# Sheet_1_2023-09-05.net
KiCad netlist of a schematic drawn in Altium Designer
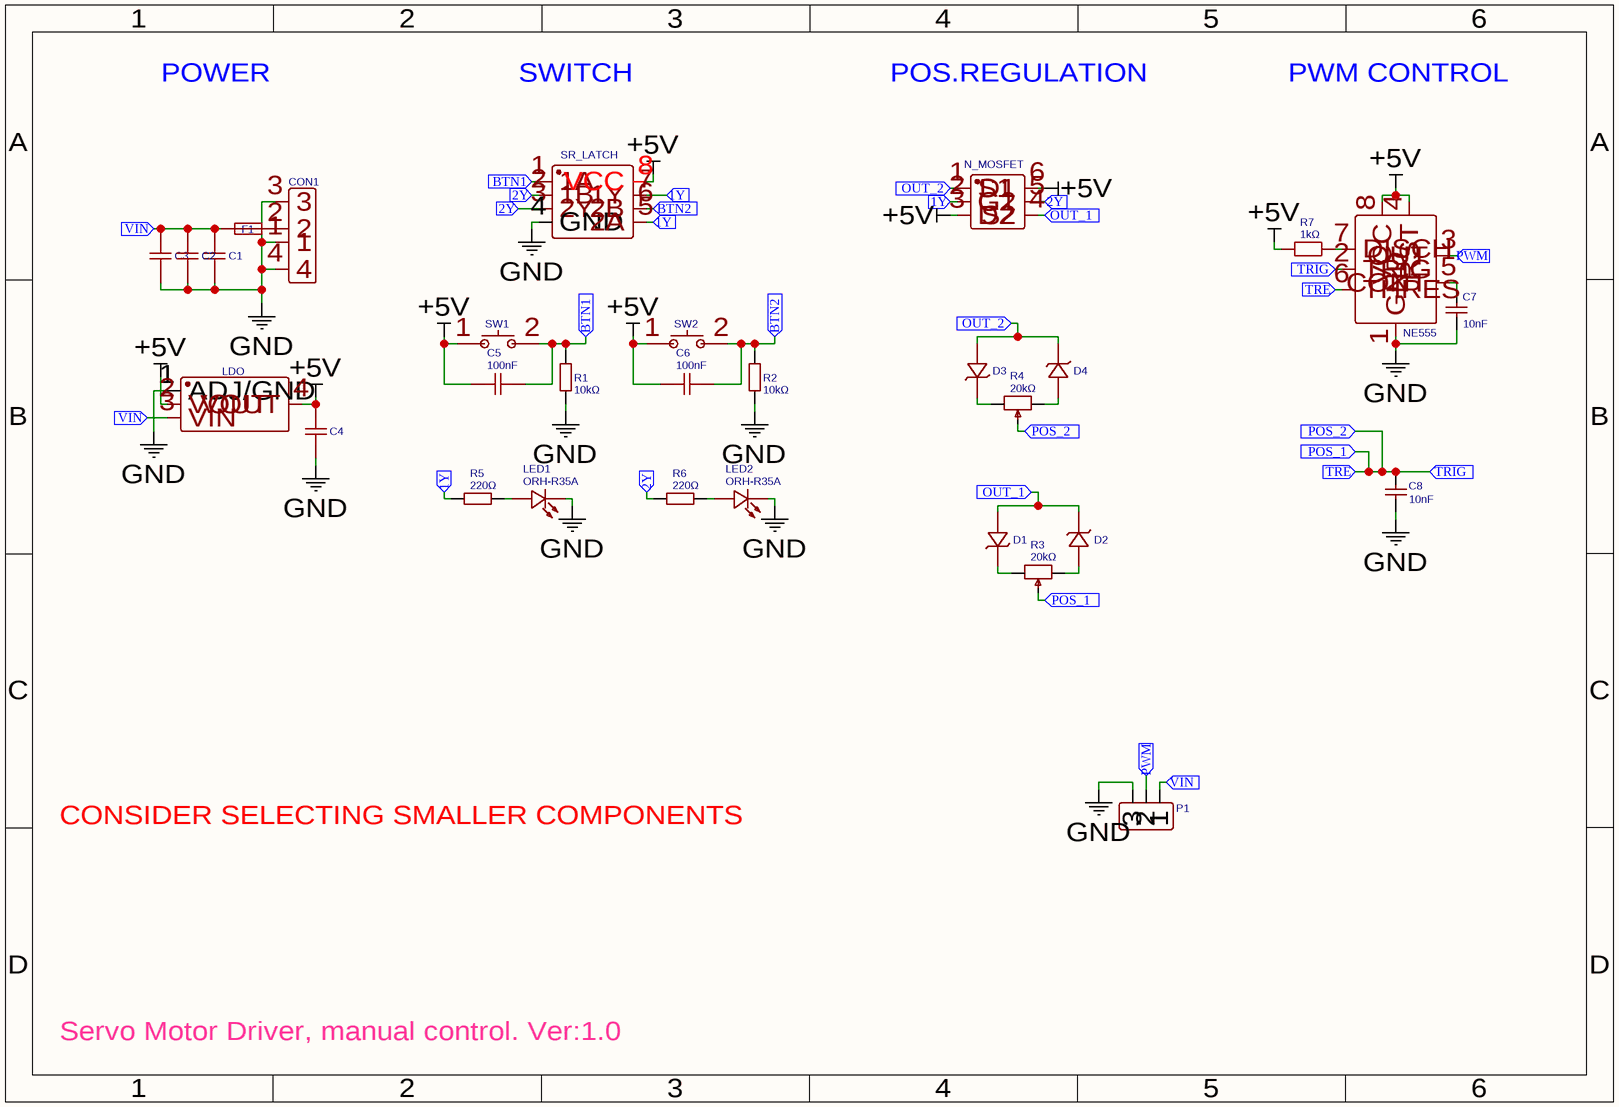
[diagram p0: Sheet_1_2023-09-05.schdoc]

(export (version "E")
  (design (tool "Eeschema 10.0.6"))
  (components
    (comp (ref "C1")
      (value "100uF")
      (fields
        (field (name "MANUFACTURER") "muRata(村田)")
        (field (name "MANUFACTURER PART") "GRM31CR61A107MEA8L")
        (field (name "CONTRIBUTOR") "lcsc")
      )
      (libsource (lib "altium-import") (part "root_1_100uF_"))
    )
    (comp (ref "C2")
      (value "100uF")
      (fields
        (field (name "MANUFACTURER") "muRata(村田)")
        (field (name "MANUFACTURER PART") "GRM31CR61A107MEA8L")
        (field (name "CONTRIBUTOR") "lcsc")
      )
      (libsource (lib "altium-import") (part "root_1_100uF_"))
    )
    (comp (ref "C3")
      (value "100uF")
      (fields
        (field (name "MANUFACTURER") "muRata(村田)")
        (field (name "MANUFACTURER PART") "GRM31CR61A107MEA8L")
        (field (name "CONTRIBUTOR") "lcsc")
      )
      (libsource (lib "altium-import") (part "root_1_100uF_"))
    )
    (comp (ref "C4")
      (value "100uF")
      (fields
        (field (name "MANUFACTURER") "muRata(村田)")
        (field (name "MANUFACTURER PART") "GRM31CR61A107MEA8L")
        (field (name "CONTRIBUTOR") "lcsc")
      )
      (libsource (lib "altium-import") (part "root_1_100uF_"))
    )
    (comp (ref "C5")
      (value "100nF")
      (fields
        (field (name "MANUFACTURER") "SAMSUNG(三星)")
        (field (name "MANUFACTURER PART") "CL10B104KB8NNNC")
      )
      (libsource (lib "altium-import") (part "root_2_100nF_"))
    )
    (comp (ref "C6")
      (value "100nF")
      (fields
        (field (name "MANUFACTURER") "SAMSUNG(三星)")
        (field (name "MANUFACTURER PART") "CL10B104KB8NNNC")
      )
      (libsource (lib "altium-import") (part "root_2_100nF_"))
    )
    (comp (ref "C7")
      (value "10nF")
      (fields (field (name "MANUFACTURER") "FH(风华)") (field (name "MANUFACTURER PART") "1206B103K102NT"))
      (libsource (lib "altium-import") (part "root_1_10nF_"))
    )
    (comp (ref "C8")
      (value "10nF")
      (fields (field (name "MANUFACTURER") "FH(风华)") (field (name "MANUFACTURER PART") "1206B103K102NT"))
      (libsource (lib "altium-import") (part "root_1_10nF_"))
    )
    (comp (ref "CON1")
      (value "SM02B-SRSS-TB (LF)(SN)")
      (fields
        (field (name "MANUFACTURER") "JST")
        (field (name "MANUFACTURER PART") "SM02B-SRSS-TB(LF)(SN)")
        (field (name "CONTRIBUTOR") "LCSC")
      )
      (libsource (lib "altium-import") (part "root_1_SM02B-SRSS-TB (LF)(SN)_"))
    )
    (comp (ref "D1")
      (value "1N4007_C727082")
      (fields
        (field (name "MANUFACTURER") "TWGMC(台湾迪嘉)")
        (field (name "MANUFACTURER PART") "1N4007")
        (field (name "CONTRIBUTOR") "LCSC")
      )
      (libsource (lib "altium-import") (part "root_1_1N4007_C727082_"))
    )
    (comp (ref "D2")
      (value "1N4007_C727082")
      (fields
        (field (name "MANUFACTURER") "TWGMC(台湾迪嘉)")
        (field (name "MANUFACTURER PART") "1N4007")
        (field (name "CONTRIBUTOR") "LCSC")
      )
      (libsource (lib "altium-import") (part "root_3_1N4007_C727082_"))
    )
    (comp (ref "D3")
      (value "1N4007_C727082")
      (fields
        (field (name "MANUFACTURER") "TWGMC(台湾迪嘉)")
        (field (name "MANUFACTURER PART") "1N4007")
        (field (name "CONTRIBUTOR") "LCSC")
      )
      (libsource (lib "altium-import") (part "root_1_1N4007_C727082_"))
    )
    (comp (ref "D4")
      (value "1N4007_C727082")
      (fields
        (field (name "MANUFACTURER") "TWGMC(台湾迪嘉)")
        (field (name "MANUFACTURER PART") "1N4007")
        (field (name "CONTRIBUTOR") "LCSC")
      )
      (libsource (lib "altium-import") (part "root_3_1N4007_C727082_"))
    )
    (comp (ref "F1")
      (value "MF-MSMF110/16-2")
      (fields (field (name "MANUFACTURER") "BOURNS") (field (name "CONTRIBUTOR") "LCSC"))
      (libsource (lib "altium-import") (part "root_0_MF-MSMF110/16-2_"))
    )
    (comp (ref "LDO")
      (value "AMS1117-5.0_C473812")
      (fields
        (field (name "MANUFACTURER") "Slkor(萨科微)")
        (field (name "MANUFACTURER PART") "AMS1117-5.0")
        (field (name "CONTRIBUTOR") "LCSC")
      )
      (libsource (lib "altium-import") (part "root_0_AMS1117-5.0_C473812_"))
    )
    (comp (ref "LED1")
      (value "ORH-R35A")
      (fields (field (name "MANUFACTURER") "Orient(奥伦德)") (field (name "CONTRIBUTOR") "LCSC"))
      (libsource (lib "altium-import") (part "root_2_ORH-R35A_"))
    )
    (comp (ref "LED2")
      (value "ORH-R35A")
      (fields (field (name "MANUFACTURER") "Orient(奥伦德)") (field (name "CONTRIBUTOR") "LCSC"))
      (libsource (lib "altium-import") (part "root_2_ORH-R35A_"))
    )
    (comp (ref "NE555")
      (value "100kHz")
      (fields (field (name "MANUFACTURER") "TI(德州仪器)") (field (name "MANUFACTURER PART") "NE555DR"))
      (libsource (lib "altium-import") (part "root_0_100kHz_"))
    )
    (comp (ref "N_MOSFET")
      (value "2N7002DWH6327XTSA1")
      (fields
        (field (name "MANUFACTURER") "Infineon(英飞凌)")
        (field (name "MANUFACTURER PART") "2N7002DWH6327")
        (field (name "CONTRIBUTOR") "LCSC")
      )
      (libsource (lib "altium-import") (part "root_0_2N7002DWH6327XTSA1_"))
    )
    (comp (ref "P1")
      (value "Header-Female-2.54_1x3")
      (fields (field (name "MANUFACTURER") "BOOMELE(博穆精密)") (field (name "MANUFACTURER PART") "2.54-1*3P母"))
      (libsource (lib "altium-import") (part "root_3_Header-Female-2.54_1x3_"))
    )
    (comp (ref "R1")
      (value "10kΩ")
      (fields
        (field (name "MANUFACTURER") "UNI-ROYAL(厚声)")
        (field (name "MANUFACTURER PART") "0603WAF1002T5E")
      )
      (libsource (lib "altium-import") (part "root_1_10kΩ_"))
    )
    (comp (ref "R2")
      (value "10kΩ")
      (fields
        (field (name "MANUFACTURER") "UNI-ROYAL(厚声)")
        (field (name "MANUFACTURER PART") "0603WAF1002T5E")
      )
      (libsource (lib "altium-import") (part "root_1_10kΩ_"))
    )
    (comp (ref "R3")
      (value "20kΩ")
      (fields (field (name "MANUFACTURER") "HDK(北陆电气)") (field (name "MANUFACTURER PART") "VG039NCHXTB203"))
      (libsource (lib "altium-import") (part "root_1_20kΩ_"))
    )
    (comp (ref "R4")
      (value "20kΩ")
      (fields (field (name "MANUFACTURER") "HDK(北陆电气)") (field (name "MANUFACTURER PART") "VG039NCHXTB203"))
      (libsource (lib "altium-import") (part "root_1_20kΩ_"))
    )
    (comp (ref "R5")
      (value "220Ω")
      (fields (field (name "MANUFACTURER") "YAGEO(国巨)") (field (name "MANUFACTURER PART") "RC0603FR-07220RL"))
      (libsource (lib "altium-import") (part "root_0_220Ω_"))
    )
    (comp (ref "R6")
      (value "220Ω")
      (fields (field (name "MANUFACTURER") "YAGEO(国巨)") (field (name "MANUFACTURER PART") "RC0603FR-07220RL"))
      (libsource (lib "altium-import") (part "root_0_220Ω_"))
    )
    (comp (ref "R7")
      (value "1kΩ")
      (fields
        (field (name "MANUFACTURER") "Viking(光颉)")
        (field (name "MANUFACTURER PART") "CR-06JA7----1K")
        (field (name "CONTRIBUTOR") "LCSC")
      )
      (libsource (lib "altium-import") (part "root_0_1kΩ_"))
    )
    (comp (ref "SR_LATCH")
      (value "SN74LVC2G02DCUR")
      (fields (field (name "MANUFACTURER") "TI(德州仪器)"))
      (libsource (lib "altium-import") (part "root_0_SN74LVC2G02DCUR_"))
    )
    (comp (ref "SW1")
      (value "GT-TC029B-H025-L1N")
      (fields (field (name "MANUFACTURER") "G-Switch(品赞)") (field (name "CONTRIBUTOR") "LCSC"))
      (libsource (lib "altium-import") (part "root_0_GT-TC029B-H025-L1N_"))
    )
    (comp (ref "SW2")
      (value "GT-TC029B-H025-L1N")
      (fields (field (name "MANUFACTURER") "G-Switch(品赞)") (field (name "CONTRIBUTOR") "LCSC"))
      (libsource (lib "altium-import") (part "root_0_GT-TC029B-H025-L1N_"))
    )
  )
  (nets
    (net (code "1") (name "+5V") (class "Default")
      (node (ref "C4") (pin "2") (pinfunction "2_2") (pintype "passive"))
      (node (ref "C5") (pin "2") (pinfunction "2_2") (pintype "passive"))
      (node (ref "C6") (pin "2") (pinfunction "2_2") (pintype "passive"))
      (node (ref "LDO") (pin "2") (pinfunction "VOUT_2") (pintype "passive"))
      (node (ref "LDO") (pin "4") (pinfunction "VOUT_4") (pintype "passive"))
      (node (ref "NE555") (pin "4") (pinfunction "RST_4") (pintype "passive"))
      (node (ref "NE555") (pin "8") (pinfunction "VCC_8") (pintype "passive"))
      (node (ref "N_MOSFET") (pin "3") (pinfunction "D2_3") (pintype "passive"))
      (node (ref "N_MOSFET") (pin "6") (pinfunction "D1_6") (pintype "passive"))
      (node (ref "R7") (pin "1") (pinfunction "1_1") (pintype "passive"))
      (node (ref "SR_LATCH") (pin "8") (pinfunction "VCC_8") (pintype "passive"))
      (node (ref "SW1") (pin "1") (pinfunction "1_1") (pintype "passive"))
      (node (ref "SW2") (pin "1") (pinfunction "1_1") (pintype "passive"))
    )
    (net (code "2") (name "/1Y") (class "Default")
      (node (ref "N_MOSFET") (pin "2") (pinfunction "G1_2") (pintype "passive"))
      (node (ref "R5") (pin "1") (pinfunction "1_1") (pintype "passive"))
      (node (ref "SR_LATCH") (pin "5") (pinfunction "2A_5") (pintype "passive"))
      (node (ref "SR_LATCH") (pin "7") (pinfunction "1Y_7") (pintype "passive"))
    )
    (net (code "3") (name "/2Y") (class "Default")
      (node (ref "N_MOSFET") (pin "5") (pinfunction "G2_5") (pintype "passive"))
      (node (ref "R6") (pin "1") (pinfunction "1_1") (pintype "passive"))
      (node (ref "SR_LATCH") (pin "2") (pinfunction "1B_2") (pintype "passive"))
      (node (ref "SR_LATCH") (pin "3") (pinfunction "2Y_3") (pintype "passive"))
    )
    (net (code "4") (name "/BTN1") (class "Default")
      (node (ref "C5") (pin "1") (pinfunction "1_1") (pintype "passive"))
      (node (ref "R1") (pin "2") (pinfunction "2_2") (pintype "passive"))
      (node (ref "SR_LATCH") (pin "1") (pinfunction "1A_1") (pintype "passive"))
      (node (ref "SW1") (pin "2") (pinfunction "2_2") (pintype "passive"))
    )
    (net (code "5") (name "/BTN2") (class "Default")
      (node (ref "C6") (pin "1") (pinfunction "1_1") (pintype "passive"))
      (node (ref "R2") (pin "2") (pinfunction "2_2") (pintype "passive"))
      (node (ref "SR_LATCH") (pin "6") (pinfunction "2B_6") (pintype "passive"))
      (node (ref "SW2") (pin "2") (pinfunction "2_2") (pintype "passive"))
    )
    (net (code "6") (name "/OUT_1") (class "Default")
      (node (ref "D1") (pin "2") (pinfunction "A_2") (pintype "passive"))
      (node (ref "D2") (pin "1") (pinfunction "K_1") (pintype "passive"))
      (node (ref "N_MOSFET") (pin "4") (pinfunction "S2_4") (pintype "passive"))
    )
    (net (code "7") (name "/OUT_2") (class "Default")
      (node (ref "D3") (pin "2") (pinfunction "A_2") (pintype "passive"))
      (node (ref "D4") (pin "1") (pinfunction "K_1") (pintype "passive"))
      (node (ref "N_MOSFET") (pin "1") (pinfunction "S1_1") (pintype "passive"))
    )
    (net (code "8") (name "/POS_1") (class "Default")
      (node (ref "C8") (pin "2") (pinfunction "2_2") (pintype "passive"))
      (node (ref "NE555") (pin "2") (pinfunction "TRIG_2") (pintype "passive"))
      (node (ref "NE555") (pin "6") (pinfunction "THRES_6") (pintype "passive"))
      (node (ref "R3") (pin "2") (pinfunction "2_2") (pintype "passive"))
      (node (ref "R4") (pin "2") (pinfunction "2_2") (pintype "passive"))
    )
    (net (code "9") (name "/PWM") (class "Default")
      (node (ref "NE555") (pin "3") (pinfunction "OUT_3") (pintype "passive"))
      (node (ref "P1") (pin "2") (pinfunction "2_2") (pintype "passive"))
    )
    (net (code "10") (name "/VIN") (class "Default")
      (node (ref "C1") (pin "2") (pinfunction "2_2") (pintype "passive"))
      (node (ref "C2") (pin "2") (pinfunction "2_2") (pintype "passive"))
      (node (ref "C3") (pin "2") (pinfunction "2_2") (pintype "passive"))
      (node (ref "F1") (pin "1") (pinfunction "1_1") (pintype "passive"))
      (node (ref "LDO") (pin "3") (pinfunction "VIN_3") (pintype "passive"))
      (node (ref "P1") (pin "1") (pinfunction "1_1") (pintype "passive"))
    )
    (net (code "11") (name "GND") (class "Default")
      (node (ref "C1") (pin "1") (pinfunction "1_1") (pintype "passive"))
      (node (ref "C2") (pin "1") (pinfunction "1_1") (pintype "passive"))
      (node (ref "C3") (pin "1") (pinfunction "1_1") (pintype "passive"))
      (node (ref "C4") (pin "1") (pinfunction "1_1") (pintype "passive"))
      (node (ref "C7") (pin "1") (pinfunction "1_1") (pintype "passive"))
      (node (ref "C8") (pin "1") (pinfunction "1_1") (pintype "passive"))
      (node (ref "CON1") (pin "1") (pinfunction "1_1") (pintype "passive"))
      (node (ref "CON1") (pin "3") (pinfunction "3_3") (pintype "passive"))
      (node (ref "CON1") (pin "4") (pinfunction "4_4") (pintype "passive"))
      (node (ref "LDO") (pin "1") (pinfunction "ADJ/GND_1") (pintype "passive"))
      (node (ref "LED1") (pin "2") (pinfunction "C_2") (pintype "passive"))
      (node (ref "LED2") (pin "2") (pinfunction "C_2") (pintype "passive"))
      (node (ref "NE555") (pin "1") (pinfunction "GND_1") (pintype "passive"))
      (node (ref "P1") (pin "3") (pinfunction "3_3") (pintype "passive"))
      (node (ref "R1") (pin "1") (pinfunction "1_1") (pintype "passive"))
      (node (ref "R2") (pin "1") (pinfunction "1_1") (pintype "passive"))
      (node (ref "SR_LATCH") (pin "4") (pinfunction "GND_4") (pintype "passive"))
    )
    (net (code "12") (name "Net-(CON1-Pad2)") (class "Default")
      (node (ref "CON1") (pin "2") (pinfunction "2_2") (pintype "passive"))
      (node (ref "F1") (pin "2") (pinfunction "2_2") (pintype "passive"))
    )
    (net (code "13") (name "Net-(D1-K)") (class "Default")
      (node (ref "D1") (pin "1") (pinfunction "K_1") (pintype "passive"))
      (node (ref "R3") (pin "3") (pinfunction "3_3") (pintype "passive"))
    )
    (net (code "14") (name "Net-(D2-A)") (class "Default")
      (node (ref "D2") (pin "2") (pinfunction "A_2") (pintype "passive"))
      (node (ref "R3") (pin "1") (pinfunction "1_1") (pintype "passive"))
    )
    (net (code "15") (name "Net-(D3-K)") (class "Default")
      (node (ref "D3") (pin "1") (pinfunction "K_1") (pintype "passive"))
      (node (ref "R4") (pin "3") (pinfunction "3_3") (pintype "passive"))
    )
    (net (code "16") (name "Net-(D4-A)") (class "Default")
      (node (ref "D4") (pin "2") (pinfunction "A_2") (pintype "passive"))
      (node (ref "R4") (pin "1") (pinfunction "1_1") (pintype "passive"))
    )
    (net (code "17") (name "Net-(LED1-A)") (class "Default")
      (node (ref "LED1") (pin "1") (pinfunction "A_1") (pintype "passive"))
      (node (ref "R5") (pin "2") (pinfunction "2_2") (pintype "passive"))
    )
    (net (code "18") (name "Net-(LED2-A)") (class "Default")
      (node (ref "LED2") (pin "1") (pinfunction "A_1") (pintype "passive"))
      (node (ref "R6") (pin "2") (pinfunction "2_2") (pintype "passive"))
    )
    (net (code "19") (name "Net-(NE555-CONT)") (class "Default")
      (node (ref "C7") (pin "2") (pinfunction "2_2") (pintype "passive"))
      (node (ref "NE555") (pin "5") (pinfunction "CONT_5") (pintype "passive"))
    )
    (net (code "20") (name "Net-(NE555-DISCH)") (class "Default")
      (node (ref "NE555") (pin "7") (pinfunction "DISCH_7") (pintype "passive"))
      (node (ref "R7") (pin "2") (pinfunction "2_2") (pintype "passive"))
    )
  )
)
